# BLDC_Controller.net
KiCad netlist of a schematic drawn in EAGLE
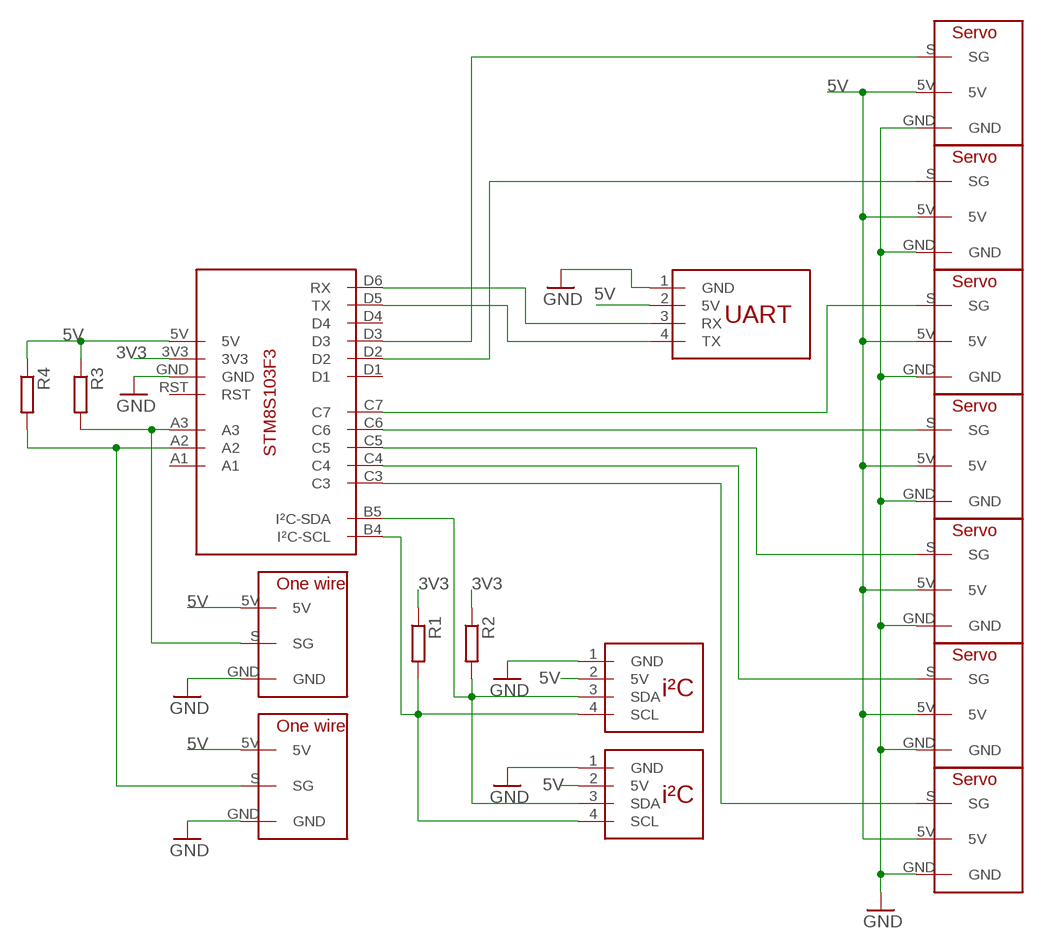
[diagram p0: schematic, sheet 1]

(export (version "E")
  (design (tool "Eeschema 10.0.6"))
  (components
    (comp (ref "R1")
      (value "1k")
      (footprint "eagle-import:R1206")
      (libsource (lib "eagle-import") (part "R-EU_R1206"))
    )
    (comp (ref "R2")
      (value "1k")
      (footprint "eagle-import:R1206")
      (libsource (lib "eagle-import") (part "R-EU_R1206"))
    )
    (comp (ref "R3")
      (value "1k")
      (footprint "eagle-import:R1206")
      (libsource (lib "eagle-import") (part "R-EU_R1206"))
    )
    (comp (ref "R4")
      (value "1k")
      (footprint "eagle-import:R1206")
      (libsource (lib "eagle-import") (part "R-EU_R1206"))
    )
    (comp (ref "U$1")
      (value "STM8S103F3-DEVKITMINI")
      (footprint "eagle-import:STM8S103F3-DEVKIT-MINI")
      (libsource (lib "eagle-import") (part "STM8S103F3-DEVKITMINI"))
    )
    (comp (ref "U$2")
      (value "SERVO")
      (footprint "eagle-import:SERVO")
      (libsource (lib "eagle-import") (part "SERVO"))
    )
    (comp (ref "U$3")
      (value "UARTMINI")
      (footprint "eagle-import:UART-MINI")
      (libsource (lib "eagle-import") (part "UARTMINI"))
    )
    (comp (ref "U$4")
      (value "I2CMINI")
      (footprint "eagle-import:I2C-MINI")
      (libsource (lib "eagle-import") (part "I2CMINI"))
    )
    (comp (ref "U$5")
      (value "ONE_WIRE")
      (footprint "eagle-import:ONE_WIRE")
      (libsource (lib "eagle-import") (part "ONE_WIRE"))
    )
    (comp (ref "U$6")
      (value "ONE_WIRE")
      (footprint "eagle-import:ONE_WIRE")
      (libsource (lib "eagle-import") (part "ONE_WIRE"))
    )
    (comp (ref "U$7")
      (value "I2CMINI")
      (footprint "eagle-import:I2C-MINI")
      (libsource (lib "eagle-import") (part "I2CMINI"))
    )
    (comp (ref "U$8")
      (value "SERVO")
      (footprint "eagle-import:SERVO")
      (libsource (lib "eagle-import") (part "SERVO"))
    )
    (comp (ref "U$9")
      (value "SERVO")
      (footprint "eagle-import:SERVO")
      (libsource (lib "eagle-import") (part "SERVO"))
    )
    (comp (ref "U$10")
      (value "SERVO")
      (footprint "eagle-import:SERVO")
      (libsource (lib "eagle-import") (part "SERVO"))
    )
    (comp (ref "U$11")
      (value "SERVO")
      (footprint "eagle-import:SERVO")
      (libsource (lib "eagle-import") (part "SERVO"))
    )
    (comp (ref "U$12")
      (value "SERVO")
      (footprint "eagle-import:SERVO")
      (libsource (lib "eagle-import") (part "SERVO"))
    )
    (comp (ref "U$13")
      (value "SERVO")
      (footprint "eagle-import:SERVO")
      (libsource (lib "eagle-import") (part "SERVO"))
    )
  )
  (nets
    (net (code "1") (name "/3V3") (class "Default")
      (node (ref "R1") (pin "1") (pinfunction "1_1") (pintype "passive"))
      (node (ref "R2") (pin "1") (pinfunction "1_1") (pintype "passive"))
      (node (ref "U$1") (pin "3V3") (pinfunction "3V3_3V3") (pintype "bidirectional"))
    )
    (net (code "2") (name "/5V") (class "Default")
      (node (ref "R3") (pin "1") (pinfunction "1_1") (pintype "passive"))
      (node (ref "R4") (pin "1") (pinfunction "1_1") (pintype "passive"))
      (node (ref "U$1") (pin "5V") (pinfunction "5V_5V") (pintype "bidirectional"))
      (node (ref "U$10") (pin "5V") (pinfunction "5V_5V") (pintype "bidirectional"))
      (node (ref "U$11") (pin "5V") (pinfunction "5V_5V") (pintype "bidirectional"))
      (node (ref "U$12") (pin "5V") (pinfunction "5V_5V") (pintype "bidirectional"))
      (node (ref "U$13") (pin "5V") (pinfunction "5V_5V") (pintype "bidirectional"))
      (node (ref "U$2") (pin "5V") (pinfunction "5V_5V") (pintype "bidirectional"))
      (node (ref "U$3") (pin "2") (pinfunction "5V_2") (pintype "bidirectional"))
      (node (ref "U$4") (pin "2") (pinfunction "5V_2") (pintype "bidirectional"))
      (node (ref "U$5") (pin "5V") (pinfunction "5V_5V") (pintype "bidirectional"))
      (node (ref "U$6") (pin "5V") (pinfunction "5V_5V") (pintype "bidirectional"))
      (node (ref "U$7") (pin "2") (pinfunction "5V_2") (pintype "bidirectional"))
      (node (ref "U$8") (pin "5V") (pinfunction "5V_5V") (pintype "bidirectional"))
      (node (ref "U$9") (pin "5V") (pinfunction "5V_5V") (pintype "bidirectional"))
    )
    (net (code "3") (name "GND") (class "Default")
      (node (ref "U$1") (pin "GND") (pinfunction "GND_GND") (pintype "bidirectional"))
      (node (ref "U$10") (pin "GND") (pinfunction "GND_GND") (pintype "bidirectional"))
      (node (ref "U$11") (pin "GND") (pinfunction "GND_GND") (pintype "bidirectional"))
      (node (ref "U$12") (pin "GND") (pinfunction "GND_GND") (pintype "bidirectional"))
      (node (ref "U$13") (pin "GND") (pinfunction "GND_GND") (pintype "bidirectional"))
      (node (ref "U$2") (pin "GND") (pinfunction "GND_GND") (pintype "bidirectional"))
      (node (ref "U$3") (pin "1") (pinfunction "GND_1") (pintype "bidirectional"))
      (node (ref "U$4") (pin "1") (pinfunction "GND_1") (pintype "bidirectional"))
      (node (ref "U$5") (pin "GND") (pinfunction "GND_GND") (pintype "bidirectional"))
      (node (ref "U$6") (pin "GND") (pinfunction "GND_GND") (pintype "bidirectional"))
      (node (ref "U$7") (pin "1") (pinfunction "GND_1") (pintype "bidirectional"))
      (node (ref "U$8") (pin "GND") (pinfunction "GND_GND") (pintype "bidirectional"))
      (node (ref "U$9") (pin "GND") (pinfunction "GND_GND") (pintype "bidirectional"))
    )
    (net (code "4") (name "Net-(U$1-I²C-SCL)") (class "Default")
      (node (ref "R1") (pin "2") (pinfunction "2_2") (pintype "passive"))
      (node (ref "U$1") (pin "B4") (pinfunction "I²C-SCL_B4") (pintype "bidirectional"))
      (node (ref "U$4") (pin "4") (pinfunction "SCL_4") (pintype "bidirectional"))
      (node (ref "U$7") (pin "4") (pinfunction "SCL_4") (pintype "bidirectional"))
    )
    (net (code "5") (name "Net-(U$1-I²C-SDA)") (class "Default")
      (node (ref "R2") (pin "2") (pinfunction "2_2") (pintype "passive"))
      (node (ref "U$1") (pin "B5") (pinfunction "I²C-SDA_B5") (pintype "bidirectional"))
      (node (ref "U$4") (pin "3") (pinfunction "SDA_3") (pintype "bidirectional"))
      (node (ref "U$7") (pin "3") (pinfunction "SDA_3") (pintype "bidirectional"))
    )
    (net (code "6") (name "Net-(U$1-RX)") (class "Default")
      (node (ref "U$1") (pin "D6") (pinfunction "RX_D6") (pintype "bidirectional"))
      (node (ref "U$3") (pin "3") (pinfunction "RX_3") (pintype "bidirectional"))
    )
    (net (code "7") (name "Net-(U$1-TX)") (class "Default")
      (node (ref "U$1") (pin "D5") (pinfunction "TX_D5") (pintype "bidirectional"))
      (node (ref "U$3") (pin "4") (pinfunction "TX_4") (pintype "bidirectional"))
    )
    (net (code "8") (name "Net-(U$2-SG)") (class "Default")
      (node (ref "U$1") (pin "D2") (pinfunction "D2_D2") (pintype "bidirectional"))
      (node (ref "U$2") (pin "S") (pinfunction "SG_S") (pintype "bidirectional"))
    )
    (net (code "9") (name "Net-(U$5-SG)") (class "Default")
      (node (ref "R4") (pin "2") (pinfunction "2_2") (pintype "passive"))
      (node (ref "U$1") (pin "A2") (pinfunction "A2_A2") (pintype "bidirectional"))
      (node (ref "U$5") (pin "S") (pinfunction "SG_S") (pintype "bidirectional"))
    )
    (net (code "10") (name "Net-(U$6-SG)") (class "Default")
      (node (ref "R3") (pin "2") (pinfunction "2_2") (pintype "passive"))
      (node (ref "U$1") (pin "A3") (pinfunction "A3_A3") (pintype "bidirectional"))
      (node (ref "U$6") (pin "S") (pinfunction "SG_S") (pintype "bidirectional"))
    )
    (net (code "11") (name "Net-(U$8-SG)") (class "Default")
      (node (ref "U$1") (pin "C7") (pinfunction "C7_C7") (pintype "bidirectional"))
      (node (ref "U$8") (pin "S") (pinfunction "SG_S") (pintype "bidirectional"))
    )
    (net (code "12") (name "Net-(U$9-SG)") (class "Default")
      (node (ref "U$1") (pin "C6") (pinfunction "C6_C6") (pintype "bidirectional"))
      (node (ref "U$9") (pin "S") (pinfunction "SG_S") (pintype "bidirectional"))
    )
    (net (code "13") (name "Net-(U$10-SG)") (class "Default")
      (node (ref "U$1") (pin "C5") (pinfunction "C5_C5") (pintype "bidirectional"))
      (node (ref "U$10") (pin "S") (pinfunction "SG_S") (pintype "bidirectional"))
    )
    (net (code "14") (name "Net-(U$11-SG)") (class "Default")
      (node (ref "U$1") (pin "D3") (pinfunction "D3_D3") (pintype "bidirectional"))
      (node (ref "U$11") (pin "S") (pinfunction "SG_S") (pintype "bidirectional"))
    )
    (net (code "15") (name "Net-(U$12-SG)") (class "Default")
      (node (ref "U$1") (pin "C4") (pinfunction "C4_C4") (pintype "bidirectional"))
      (node (ref "U$12") (pin "S") (pinfunction "SG_S") (pintype "bidirectional"))
    )
    (net (code "16") (name "Net-(U$13-SG)") (class "Default")
      (node (ref "U$1") (pin "C3") (pinfunction "C3_C3") (pintype "bidirectional"))
      (node (ref "U$13") (pin "S") (pinfunction "SG_S") (pintype "bidirectional"))
    )
    (net (code "17") (name "unconnected-(U$1-PadA1)") (class "Default")
      (node (ref "U$1") (pin "A1") (pinfunction "A1_A1") (pintype "bidirectional"))
    )
    (net (code "18") (name "unconnected-(U$1-PadD1)") (class "Default")
      (node (ref "U$1") (pin "D1") (pinfunction "D1_D1") (pintype "bidirectional"))
    )
    (net (code "19") (name "unconnected-(U$1-PadD4)") (class "Default")
      (node (ref "U$1") (pin "D4") (pinfunction "D4_D4") (pintype "bidirectional"))
    )
    (net (code "20") (name "unconnected-(U$1-PadRST)") (class "Default")
      (node (ref "U$1") (pin "RST") (pinfunction "RST_RST") (pintype "bidirectional"))
    )
  )
)
